# microzed_sd_v0_3_47bf9eb6.net
KiCad netlist of a schematic drawn in EAGLE
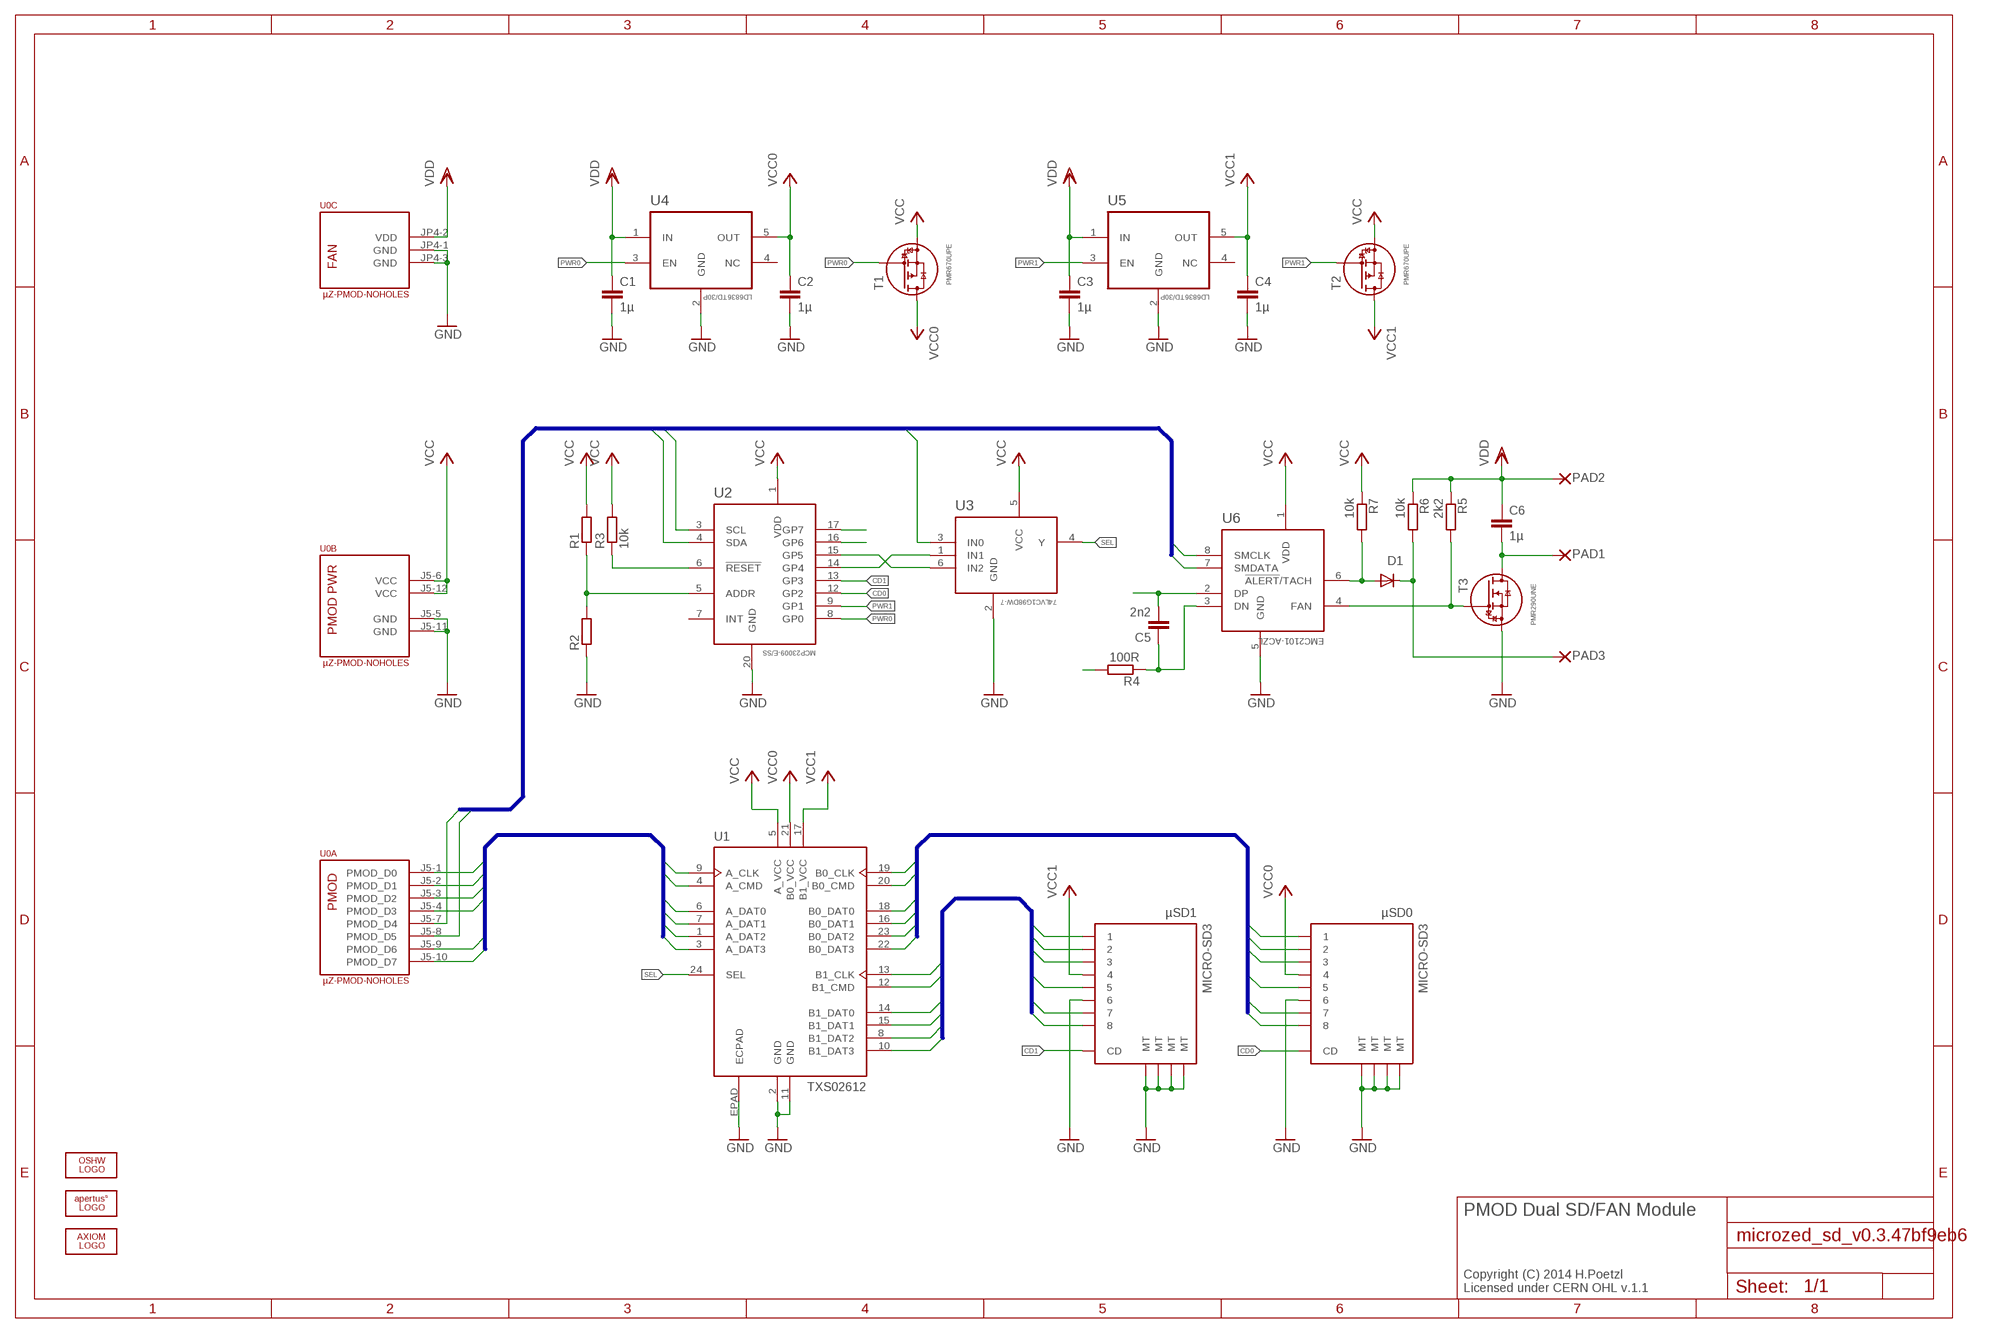
[diagram p0: schematic, sheet 1]

(export (version "E")
  (design (tool "Eeschema 10.0.6"))
  (components
    (comp (ref "C1")
      (value "1µ")
      (footprint "eagle-import:C0402K")
      (libsource (lib "eagle-import") (part "C-EUC0402K"))
    )
    (comp (ref "C2")
      (value "1µ")
      (footprint "eagle-import:C0402K")
      (libsource (lib "eagle-import") (part "C-EUC0402K"))
    )
    (comp (ref "C3")
      (value "1µ")
      (footprint "eagle-import:C0402K")
      (libsource (lib "eagle-import") (part "C-EUC0402K"))
    )
    (comp (ref "C4")
      (value "1µ")
      (footprint "eagle-import:C0402K")
      (libsource (lib "eagle-import") (part "C-EUC0402K"))
    )
    (comp (ref "C5")
      (value "2n2")
      (footprint "eagle-import:C0402K")
      (libsource (lib "eagle-import") (part "C-EUC0402K"))
    )
    (comp (ref "C6")
      (value "1µ")
      (footprint "eagle-import:C0402K")
      (libsource (lib "eagle-import") (part "C-EUC0402K"))
    )
    (comp (ref "D1")
      (value "DIODE-MICROMELF-W")
      (footprint "eagle-import:MICROMELF-W")
      (libsource (lib "eagle-import") (part "DIODE-MICROMELF-W"))
    )
    (comp (ref "LOGO1")
      (value "OSHW_LOGO_FILLX0100-NT")
      (footprint "eagle-import:OSHW_FILLX100_NOTEXT")
      (libsource (lib "eagle-import") (part "OSHW_LOGO_FILLX0100-NT"))
    )
    (comp (ref "PAD1")
      (value "WIREPAD2,15/1,0")
      (footprint "eagle-import:2,15_1,0")
      (libsource (lib "eagle-import") (part "WIREPAD2,15/1,0"))
    )
    (comp (ref "PAD2")
      (value "WIREPAD2,15/1,0")
      (footprint "eagle-import:2,15_1,0")
      (libsource (lib "eagle-import") (part "WIREPAD2,15/1,0"))
    )
    (comp (ref "PAD3")
      (value "WIREPAD2,15/1,0")
      (footprint "eagle-import:2,15_1,0")
      (libsource (lib "eagle-import") (part "WIREPAD2,15/1,0"))
    )
    (comp (ref "R1")
      (value "R-EU_R0603")
      (footprint "eagle-import:R0603")
      (libsource (lib "eagle-import") (part "R-EU_R0603"))
    )
    (comp (ref "R2")
      (value "R-EU_R0603")
      (footprint "eagle-import:R0603")
      (libsource (lib "eagle-import") (part "R-EU_R0603"))
    )
    (comp (ref "R3")
      (value "10k")
      (footprint "eagle-import:R0603")
      (libsource (lib "eagle-import") (part "R-EU_R0603"))
    )
    (comp (ref "R4")
      (value "100R")
      (footprint "eagle-import:R0402")
      (libsource (lib "eagle-import") (part "R-EU_R0402"))
    )
    (comp (ref "R5")
      (value "2k2")
      (footprint "eagle-import:R0402")
      (libsource (lib "eagle-import") (part "R-EU_R0402"))
    )
    (comp (ref "R6")
      (value "10k")
      (footprint "eagle-import:R0402")
      (libsource (lib "eagle-import") (part "R-EU_R0402"))
    )
    (comp (ref "R7")
      (value "10k")
      (footprint "eagle-import:R0402")
      (libsource (lib "eagle-import") (part "R-EU_R0402"))
    )
    (comp (ref "T1")
      (value "PMR670UPE")
      (footprint "eagle-import:SOT416")
      (libsource (lib "eagle-import") (part "PMR670UPE"))
    )
    (comp (ref "T2")
      (value "PMR670UPE")
      (footprint "eagle-import:SOT416")
      (libsource (lib "eagle-import") (part "PMR670UPE"))
    )
    (comp (ref "T3")
      (value "PMR290UNE")
      (footprint "eagle-import:SOT416")
      (libsource (lib "eagle-import") (part "PMR290UNE"))
    )
    (comp (ref "U$1")
      (value "APERTUS_LOGO334X100")
      (footprint "eagle-import:APERTUS_LOGO_334X100")
      (libsource (lib "eagle-import") (part "APERTUS_LOGO334X100"))
    )
    (comp (ref "U$13")
      (value "AXIOM_LOGO525X80")
      (footprint "eagle-import:AXIOM_LOGO_525X80")
      (libsource (lib "eagle-import") (part "AXIOM_LOGO525X80"))
    )
    (comp (ref "U0")
      (value "µZ-PMOD-NOHOLES")
      (footprint "eagle-import:µZ-TOP-NOHOLES")
      (libsource (lib "eagle-import") (part "µZ-PMOD-NOHOLES"))
    )
    (comp (ref "U1")
      (value "TXS02612")
      (footprint "eagle-import:S-PWQFN-N24")
      (libsource (lib "eagle-import") (part "TXS02612"))
    )
    (comp (ref "U2")
      (value "MCP23009-E/SS")
      (footprint "eagle-import:SOP65P780X200-20N")
      (libsource (lib "eagle-import") (part "MCP23009-E/SS"))
    )
    (comp (ref "U3")
      (value "74LVC1G98DW-7")
      (footprint "eagle-import:SOT65P210X110-6N")
      (libsource (lib "eagle-import") (part "74LVC1G98DW-7"))
    )
    (comp (ref "U4")
      (value "LD6836TD/30P")
      (footprint "eagle-import:SOT95P275X110-5N")
      (libsource (lib "eagle-import") (part "LD6836TD/30P"))
    )
    (comp (ref "U5")
      (value "LD6836TD/30P")
      (footprint "eagle-import:SOT95P275X110-5N")
      (libsource (lib "eagle-import") (part "LD6836TD/30P"))
    )
    (comp (ref "U6")
      (value "EMC2101-ACZL")
      (footprint "eagle-import:SOP65P490X110-8N")
      (fields (field (name "MPN") "EMC2101-ACZL-TR "))
      (libsource (lib "eagle-import") (part "EMC2101-ACZL"))
    )
    (comp (ref "µSD0")
      (value "MICRO-SD3")
      (footprint "eagle-import:TF-MICRO-SD_PP3")
      (libsource (lib "eagle-import") (part "MICRO-SD3"))
    )
    (comp (ref "µSD1")
      (value "MICRO-SD3")
      (footprint "eagle-import:TF-MICRO-SD_PP3")
      (libsource (lib "eagle-import") (part "MICRO-SD3"))
    )
  )
  (nets
    (net (code "1") (name "/A_CLK") (class "Default")
      (node (ref "U0") (pin "J5-4") (pinfunction "PMOD_D3_J5-4") (pintype "bidirectional"))
      (node (ref "U1") (pin "9") (pinfunction "A_CLK_9") (pintype "input"))
    )
    (net (code "2") (name "/A_CMD") (class "Default")
      (node (ref "U0") (pin "J5-3") (pinfunction "PMOD_D2_J5-3") (pintype "bidirectional"))
      (node (ref "U1") (pin "4") (pinfunction "A_CMD_4") (pintype "bidirectional"))
    )
    (net (code "3") (name "/A_DAT0") (class "Default")
      (node (ref "U0") (pin "J5-2") (pinfunction "PMOD_D1_J5-2") (pintype "bidirectional"))
      (node (ref "U1") (pin "6") (pinfunction "A_DAT0_6") (pintype "bidirectional"))
    )
    (net (code "4") (name "/A_DAT1") (class "Default")
      (node (ref "U0") (pin "J5-1") (pinfunction "PMOD_D0_J5-1") (pintype "bidirectional"))
      (node (ref "U1") (pin "7") (pinfunction "A_DAT1_7") (pintype "bidirectional"))
    )
    (net (code "5") (name "/A_DAT2") (class "Default")
      (node (ref "U0") (pin "J5-9") (pinfunction "PMOD_D6_J5-9") (pintype "bidirectional"))
      (node (ref "U1") (pin "1") (pinfunction "A_DAT2_1") (pintype "bidirectional"))
    )
    (net (code "6") (name "/A_DAT3") (class "Default")
      (node (ref "U0") (pin "J5-10") (pinfunction "PMOD_D7_J5-10") (pintype "bidirectional"))
      (node (ref "U1") (pin "3") (pinfunction "A_DAT3_3") (pintype "bidirectional"))
    )
    (net (code "7") (name "/B0_CLK") (class "Default")
      (node (ref "U1") (pin "19") (pinfunction "B0_CLK_19") (pintype "output"))
      (node (ref "µSD0") (pin "5") (pinfunction "5_5") (pintype "bidirectional"))
    )
    (net (code "8") (name "/B0_CMD") (class "Default")
      (node (ref "U1") (pin "20") (pinfunction "B0_CMD_20") (pintype "bidirectional"))
      (node (ref "µSD0") (pin "3") (pinfunction "3_3") (pintype "bidirectional"))
    )
    (net (code "9") (name "/B0_DAT0") (class "Default")
      (node (ref "U1") (pin "18") (pinfunction "B0_DAT0_18") (pintype "bidirectional"))
      (node (ref "µSD0") (pin "7") (pinfunction "7_7") (pintype "bidirectional"))
    )
    (net (code "10") (name "/B0_DAT1") (class "Default")
      (node (ref "U1") (pin "16") (pinfunction "B0_DAT1_16") (pintype "bidirectional"))
      (node (ref "µSD0") (pin "8") (pinfunction "8_8") (pintype "bidirectional"))
    )
    (net (code "11") (name "/B0_DAT2") (class "Default")
      (node (ref "U1") (pin "23") (pinfunction "B0_DAT2_23") (pintype "bidirectional"))
      (node (ref "µSD0") (pin "1") (pinfunction "1_1") (pintype "bidirectional"))
    )
    (net (code "12") (name "/B0_DAT3") (class "Default")
      (node (ref "U1") (pin "22") (pinfunction "B0_DAT3_22") (pintype "bidirectional"))
      (node (ref "µSD0") (pin "2") (pinfunction "2_2") (pintype "bidirectional"))
    )
    (net (code "13") (name "/B1_CLK") (class "Default")
      (node (ref "U1") (pin "13") (pinfunction "B1_CLK_13") (pintype "output"))
      (node (ref "µSD1") (pin "5") (pinfunction "5_5") (pintype "bidirectional"))
    )
    (net (code "14") (name "/B1_CMD") (class "Default")
      (node (ref "U1") (pin "12") (pinfunction "B1_CMD_12") (pintype "bidirectional"))
      (node (ref "µSD1") (pin "3") (pinfunction "3_3") (pintype "bidirectional"))
    )
    (net (code "15") (name "/B1_DAT0") (class "Default")
      (node (ref "U1") (pin "14") (pinfunction "B1_DAT0_14") (pintype "bidirectional"))
      (node (ref "µSD1") (pin "7") (pinfunction "7_7") (pintype "bidirectional"))
    )
    (net (code "16") (name "/B1_DAT1") (class "Default")
      (node (ref "U1") (pin "15") (pinfunction "B1_DAT1_15") (pintype "bidirectional"))
      (node (ref "µSD1") (pin "8") (pinfunction "8_8") (pintype "bidirectional"))
    )
    (net (code "17") (name "/B1_DAT2") (class "Default")
      (node (ref "U1") (pin "8") (pinfunction "B1_DAT2_8") (pintype "bidirectional"))
      (node (ref "µSD1") (pin "1") (pinfunction "1_1") (pintype "bidirectional"))
    )
    (net (code "18") (name "/B1_DAT3") (class "Default")
      (node (ref "U1") (pin "10") (pinfunction "B1_DAT3_10") (pintype "bidirectional"))
      (node (ref "µSD1") (pin "2") (pinfunction "2_2") (pintype "bidirectional"))
    )
    (net (code "19") (name "/SCL") (class "Default")
      (node (ref "U0") (pin "J5-7") (pinfunction "PMOD_D4_J5-7") (pintype "bidirectional"))
      (node (ref "U2") (pin "3") (pinfunction "SCL_3") (pintype "input"))
      (node (ref "U6") (pin "8") (pinfunction "SMCLK_8") (pintype "input"))
    )
    (net (code "20") (name "/SDA") (class "Default")
      (node (ref "U0") (pin "J5-8") (pinfunction "PMOD_D5_J5-8") (pintype "bidirectional"))
      (node (ref "U2") (pin "4") (pinfunction "SDA_4") (pintype "bidirectional"))
      (node (ref "U3") (pin "3") (pinfunction "IN0_3") (pintype "input"))
      (node (ref "U6") (pin "7") (pinfunction "SMDATA_7") (pintype "bidirectional"))
    )
    (net (code "21") (name "CD0") (class "Default")
      (node (ref "U2") (pin "12") (pinfunction "GP2_12") (pintype "bidirectional"))
      (node (ref "µSD0") (pin "CD") (pinfunction "CD_CD") (pintype "bidirectional"))
    )
    (net (code "22") (name "CD1") (class "Default")
      (node (ref "U2") (pin "13") (pinfunction "GP3_13") (pintype "bidirectional"))
      (node (ref "µSD1") (pin "CD") (pinfunction "CD_CD") (pintype "bidirectional"))
    )
    (net (code "23") (name "GND") (class "Default")
      (node (ref "C1") (pin "2") (pinfunction "2_2") (pintype "passive"))
      (node (ref "C2") (pin "2") (pinfunction "2_2") (pintype "passive"))
      (node (ref "C3") (pin "2") (pinfunction "2_2") (pintype "passive"))
      (node (ref "C4") (pin "2") (pinfunction "2_2") (pintype "passive"))
      (node (ref "R2") (pin "1") (pinfunction "1_1") (pintype "passive"))
      (node (ref "T3") (pin "2") (pinfunction "S_2") (pintype "passive"))
      (node (ref "U0") (pin "J5-11") (pinfunction "GND_J5-11") (pintype "power_in"))
      (node (ref "U0") (pin "J5-5") (pinfunction "GND_J5-5") (pintype "power_in"))
      (node (ref "U0") (pin "JP4-1") (pinfunction "GND_JP4-1") (pintype "power_in"))
      (node (ref "U0") (pin "JP4-3") (pinfunction "GND_JP4-3") (pintype "power_in"))
      (node (ref "U1") (pin "11") (pinfunction "GND_11") (pintype "power_in"))
      (node (ref "U1") (pin "2") (pinfunction "GND_2") (pintype "power_in"))
      (node (ref "U1") (pin "EPAD") (pinfunction "ECPAD_EPAD") (pintype "power_in"))
      (node (ref "U2") (pin "20") (pinfunction "GND_20") (pintype "power_in"))
      (node (ref "U3") (pin "2") (pinfunction "GND_2") (pintype "passive"))
      (node (ref "U4") (pin "2") (pinfunction "GND_2") (pintype "passive"))
      (node (ref "U5") (pin "2") (pinfunction "GND_2") (pintype "passive"))
      (node (ref "U6") (pin "5") (pinfunction "GND_5") (pintype "power_in"))
      (node (ref "µSD0") (pin "6") (pinfunction "6_6") (pintype "bidirectional"))
      (node (ref "µSD0") (pin "MT1") (pinfunction "MT_MT1") (pintype "power_in"))
      (node (ref "µSD0") (pin "MT2") (pinfunction "MT_MT2") (pintype "power_in"))
      (node (ref "µSD0") (pin "MT3") (pinfunction "MT_MT3") (pintype "power_in"))
      (node (ref "µSD0") (pin "MT4") (pinfunction "MT_MT4") (pintype "power_in"))
      (node (ref "µSD1") (pin "6") (pinfunction "6_6") (pintype "bidirectional"))
      (node (ref "µSD1") (pin "MT1") (pinfunction "MT_MT1") (pintype "power_in"))
      (node (ref "µSD1") (pin "MT2") (pinfunction "MT_MT2") (pintype "power_in"))
      (node (ref "µSD1") (pin "MT3") (pinfunction "MT_MT3") (pintype "power_in"))
      (node (ref "µSD1") (pin "MT4") (pinfunction "MT_MT4") (pintype "power_in"))
    )
    (net (code "24") (name "Net-(PAD1-P)") (class "Default")
      (node (ref "C6") (pin "2") (pinfunction "2_2") (pintype "passive"))
      (node (ref "PAD1") (pin "1") (pinfunction "P_1") (pintype "passive"))
      (node (ref "T3") (pin "3") (pinfunction "D_3") (pintype "passive"))
    )
    (net (code "25") (name "Net-(PAD3-P)") (class "Default")
      (node (ref "D1") (pin "C") (pinfunction "C_C") (pintype "passive"))
      (node (ref "PAD3") (pin "1") (pinfunction "P_1") (pintype "passive"))
      (node (ref "R6") (pin "2") (pinfunction "2_2") (pintype "passive"))
    )
    (net (code "26") (name "Net-(T3-G)") (class "Default")
      (node (ref "R5") (pin "2") (pinfunction "2_2") (pintype "passive"))
      (node (ref "T3") (pin "1") (pinfunction "G_1") (pintype "passive"))
      (node (ref "U6") (pin "4") (pinfunction "FAN_4") (pintype "output"))
    )
    (net (code "27") (name "Net-(U2-ADDR)") (class "Default")
      (node (ref "R1") (pin "1") (pinfunction "1_1") (pintype "passive"))
      (node (ref "R2") (pin "2") (pinfunction "2_2") (pintype "passive"))
      (node (ref "U2") (pin "5") (pinfunction "ADDR_5") (pintype "input"))
    )
    (net (code "28") (name "Net-(U2-GP4)") (class "Default")
      (node (ref "U2") (pin "14") (pinfunction "GP4_14") (pintype "bidirectional"))
      (node (ref "U3") (pin "1") (pinfunction "IN1_1") (pintype "input"))
    )
    (net (code "29") (name "Net-(U2-GP5)") (class "Default")
      (node (ref "U2") (pin "15") (pinfunction "GP5_15") (pintype "bidirectional"))
      (node (ref "U3") (pin "6") (pinfunction "IN2_6") (pintype "input"))
    )
    (net (code "30") (name "Net-(U2-~{RESET})") (class "Default")
      (node (ref "R3") (pin "1") (pinfunction "1_1") (pintype "passive"))
      (node (ref "U2") (pin "6") (pinfunction "~{RESET}_6") (pintype "input"))
    )
    (net (code "31") (name "Net-(U6-DN)") (class "Default")
      (node (ref "C5") (pin "1") (pinfunction "1_1") (pintype "passive"))
      (node (ref "R4") (pin "1") (pinfunction "1_1") (pintype "passive"))
      (node (ref "U6") (pin "3") (pinfunction "DN_3") (pintype "passive"))
    )
    (net (code "32") (name "Net-(U6-DP)") (class "Default")
      (node (ref "C5") (pin "2") (pinfunction "2_2") (pintype "passive"))
      (node (ref "U6") (pin "2") (pinfunction "DP_2") (pintype "passive"))
    )
    (net (code "33") (name "Net-(U6-~{ALERT}{slash}TACH)") (class "Default")
      (node (ref "D1") (pin "A") (pinfunction "A_A") (pintype "passive"))
      (node (ref "R7") (pin "2") (pinfunction "2_2") (pintype "passive"))
      (node (ref "U6") (pin "6") (pinfunction "~{ALERT}/TACH_6") (pintype "bidirectional"))
    )
    (net (code "34") (name "PWR0") (class "Default")
      (node (ref "T1") (pin "1") (pinfunction "G_1") (pintype "passive"))
      (node (ref "U2") (pin "8") (pinfunction "GP0_8") (pintype "bidirectional"))
      (node (ref "U4") (pin "3") (pinfunction "EN_3") (pintype "input"))
    )
    (net (code "35") (name "PWR1") (class "Default")
      (node (ref "T2") (pin "1") (pinfunction "G_1") (pintype "passive"))
      (node (ref "U2") (pin "9") (pinfunction "GP1_9") (pintype "bidirectional"))
      (node (ref "U5") (pin "3") (pinfunction "EN_3") (pintype "input"))
    )
    (net (code "36") (name "SEL") (class "Default")
      (node (ref "U1") (pin "24") (pinfunction "SEL_24") (pintype "input"))
      (node (ref "U3") (pin "4") (pinfunction "Y_4") (pintype "output"))
    )
    (net (code "37") (name "VCC") (class "Default")
      (node (ref "R1") (pin "2") (pinfunction "2_2") (pintype "passive"))
      (node (ref "R3") (pin "2") (pinfunction "2_2") (pintype "passive"))
      (node (ref "R7") (pin "1") (pinfunction "1_1") (pintype "passive"))
      (node (ref "T1") (pin "2") (pinfunction "S_2") (pintype "passive"))
      (node (ref "T2") (pin "2") (pinfunction "S_2") (pintype "passive"))
      (node (ref "U0") (pin "J5-12") (pinfunction "VCC_J5-12") (pintype "power_in"))
      (node (ref "U0") (pin "J5-6") (pinfunction "VCC_J5-6") (pintype "power_in"))
      (node (ref "U1") (pin "5") (pinfunction "A_VCC_5") (pintype "power_in"))
      (node (ref "U2") (pin "1") (pinfunction "VDD_1") (pintype "power_in"))
      (node (ref "U3") (pin "5") (pinfunction "VCC_5") (pintype "power_in"))
      (node (ref "U6") (pin "1") (pinfunction "VDD_1") (pintype "power_in"))
    )
    (net (code "38") (name "VCC0") (class "Default")
      (node (ref "C2") (pin "1") (pinfunction "1_1") (pintype "passive"))
      (node (ref "T1") (pin "3") (pinfunction "D_3") (pintype "passive"))
      (node (ref "U1") (pin "21") (pinfunction "B0_VCC_21") (pintype "power_in"))
      (node (ref "U4") (pin "5") (pinfunction "OUT_5") (pintype "output"))
      (node (ref "µSD0") (pin "4") (pinfunction "4_4") (pintype "bidirectional"))
    )
    (net (code "39") (name "VCC1") (class "Default")
      (node (ref "C4") (pin "1") (pinfunction "1_1") (pintype "passive"))
      (node (ref "T2") (pin "3") (pinfunction "D_3") (pintype "passive"))
      (node (ref "U1") (pin "17") (pinfunction "B1_VCC_17") (pintype "power_in"))
      (node (ref "U5") (pin "5") (pinfunction "OUT_5") (pintype "output"))
      (node (ref "µSD1") (pin "4") (pinfunction "4_4") (pintype "bidirectional"))
    )
    (net (code "40") (name "VDD") (class "Default")
      (node (ref "C1") (pin "1") (pinfunction "1_1") (pintype "passive"))
      (node (ref "C3") (pin "1") (pinfunction "1_1") (pintype "passive"))
      (node (ref "C6") (pin "1") (pinfunction "1_1") (pintype "passive"))
      (node (ref "PAD2") (pin "1") (pinfunction "P_1") (pintype "passive"))
      (node (ref "R5") (pin "1") (pinfunction "1_1") (pintype "passive"))
      (node (ref "R6") (pin "1") (pinfunction "1_1") (pintype "passive"))
      (node (ref "U0") (pin "JP4-2") (pinfunction "VDD_JP4-2") (pintype "power_in"))
      (node (ref "U4") (pin "1") (pinfunction "IN_1") (pintype "input"))
      (node (ref "U5") (pin "1") (pinfunction "IN_1") (pintype "input"))
    )
    (net (code "41") (name "unconnected-(R4-Pad2)") (class "Default")
      (node (ref "R4") (pin "2") (pinfunction "2_2") (pintype "passive"))
    )
    (net (code "42") (name "unconnected-(U2-GP6-Pad16)") (class "Default")
      (node (ref "U2") (pin "16") (pinfunction "GP6_16") (pintype "bidirectional"))
    )
    (net (code "43") (name "unconnected-(U2-GP7-Pad17)") (class "Default")
      (node (ref "U2") (pin "17") (pinfunction "GP7_17") (pintype "bidirectional"))
    )
    (net (code "44") (name "unconnected-(U2-INT-Pad7)") (class "Default")
      (node (ref "U2") (pin "7") (pinfunction "INT_7") (pintype "output"))
    )
    (net (code "45") (name "unconnected-(U4-NC-Pad4)") (class "Default")
      (node (ref "U4") (pin "4") (pinfunction "NC_4") (pintype "no_connect"))
    )
    (net (code "46") (name "unconnected-(U5-NC-Pad4)") (class "Default")
      (node (ref "U5") (pin "4") (pinfunction "NC_4") (pintype "no_connect"))
    )
  )
)
